# Nikon_PowerBoardV2.net
KiCad netlist of a schematic drawn in EAGLE
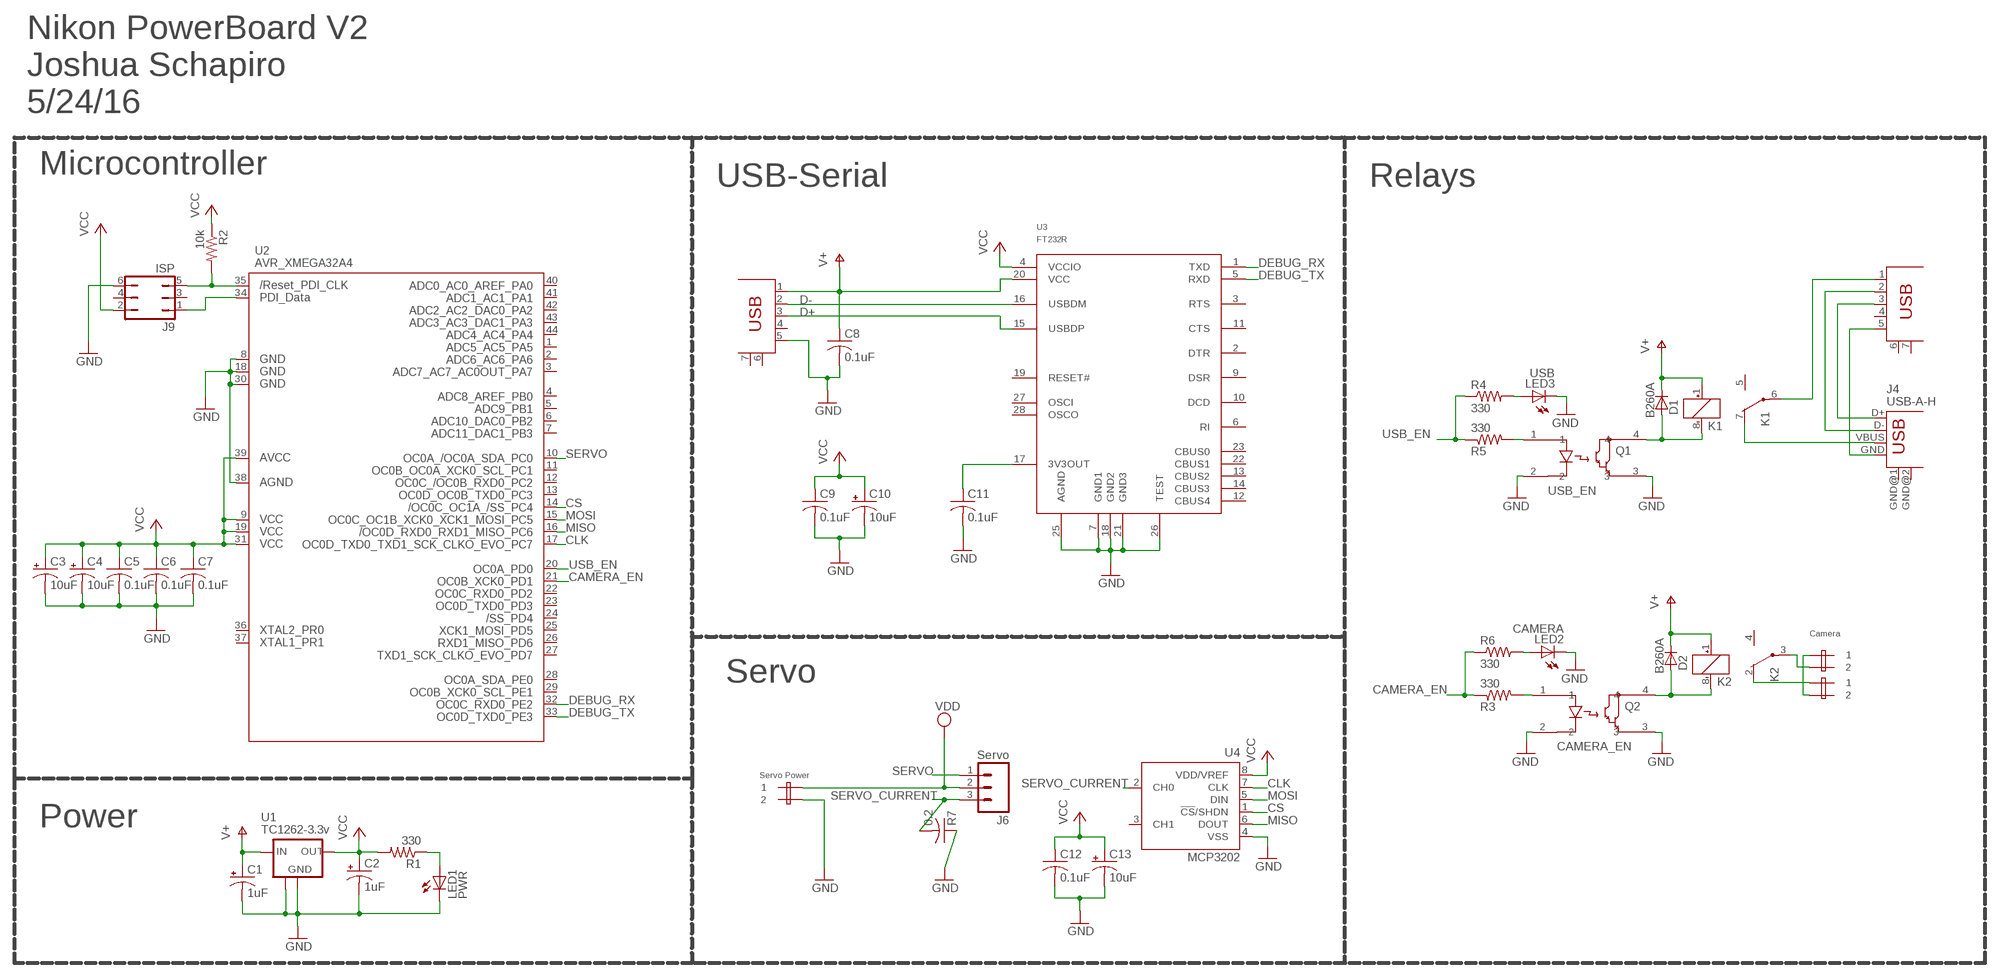
[diagram p0: schematic, sheet 1]

(export (version "E")
  (design (tool "Eeschema 10.0.6"))
  (components
    (comp (ref "C1")
      (value "1uF")
      (footprint "eagle-import:EIA3216")
      (libsource (lib "eagle-import") (part "CAP_POL1206"))
    )
    (comp (ref "C2")
      (value "1uF")
      (footprint "eagle-import:EIA3216")
      (libsource (lib "eagle-import") (part "CAP_POL1206"))
    )
    (comp (ref "C3")
      (value "10uF")
      (footprint "eagle-import:EIA3216")
      (libsource (lib "eagle-import") (part "CAP_POL1206"))
    )
    (comp (ref "C4")
      (value "10uF")
      (footprint "eagle-import:EIA3216")
      (libsource (lib "eagle-import") (part "CAP_POL1206"))
    )
    (comp (ref "C5")
      (value "0.1uF")
      (footprint "eagle-import:C0603")
      (libsource (lib "eagle-import") (part "C-USC0603"))
    )
    (comp (ref "C6")
      (value "0.1uF")
      (footprint "eagle-import:C0603")
      (libsource (lib "eagle-import") (part "resistor_C-USC0603"))
    )
    (comp (ref "C7")
      (value "0.1uF")
      (footprint "eagle-import:C0603")
      (libsource (lib "eagle-import") (part "resistor_C-USC0603"))
    )
    (comp (ref "C8")
      (value "0.1uF")
      (footprint "eagle-import:C0603")
      (libsource (lib "eagle-import") (part "resistor_C-USC0603"))
    )
    (comp (ref "C9")
      (value "0.1uF")
      (footprint "eagle-import:C0603")
      (libsource (lib "eagle-import") (part "resistor_C-USC0603"))
    )
    (comp (ref "C10")
      (value "10uF")
      (footprint "eagle-import:EIA3216")
      (libsource (lib "eagle-import") (part "CAP_POL1206"))
    )
    (comp (ref "C11")
      (value "0.1uF")
      (footprint "eagle-import:C0603")
      (libsource (lib "eagle-import") (part "resistor_C-USC0603"))
    )
    (comp (ref "C12")
      (value "0.1uF")
      (footprint "eagle-import:C0603")
      (libsource (lib "eagle-import") (part "resistor_C-USC0603"))
    )
    (comp (ref "C13")
      (value "10uF")
      (footprint "eagle-import:EIA3216")
      (libsource (lib "eagle-import") (part "CAP_POL1206"))
    )
    (comp (ref "D1")
      (value "B260A")
      (footprint "eagle-import:SMA-DIODE")
      (libsource (lib "eagle-import") (part "DIODESMA"))
    )
    (comp (ref "D2")
      (value "B260A")
      (footprint "eagle-import:SMA-DIODE")
      (libsource (lib "eagle-import") (part "DIODESMA"))
    )
    (comp (ref "J1")
      (value "Camera")
      (footprint "eagle-import:2-PIN_SCREWTERM")
      (libsource (lib "eagle-import") (part "2-PIN_SCREWTERMINAL"))
    )
    (comp (ref "J2")
      (value "Camera")
      (footprint "eagle-import:2-PIN_SCREWTERM")
      (libsource (lib "eagle-import") (part "2-PIN_SCREWTERMINAL"))
    )
    (comp (ref "J4")
      (value "USB-A-H")
      (footprint "eagle-import:USB-A-H")
      (libsource (lib "eagle-import") (part "USB-A-H"))
    )
    (comp (ref "J5")
      (value "SERVO")
      (footprint "eagle-import:2-PIN_SCREWTERM")
      (libsource (lib "eagle-import") (part "2-PIN_SCREWTERMINAL"))
    )
    (comp (ref "J6")
      (value "Servo")
      (footprint "eagle-import:1X03_LONGPADS")
      (libsource (lib "eagle-import") (part "M03LONGPADS"))
    )
    (comp (ref "J7")
      (value "MICRO-USB")
      (footprint "eagle-import:MICRO_USB_SM_W__TO_PINS")
      (libsource (lib "eagle-import") (part "MICRO-USBTO_SUPPORT"))
    )
    (comp (ref "J8")
      (value "MICRO-USB")
      (footprint "eagle-import:MICRO_USB_SM_W__TO_PINS")
      (libsource (lib "eagle-import") (part "MICRO-USBTO_SUPPORT"))
    )
    (comp (ref "J9")
      (value "ISP")
      (footprint "eagle-import:JP3Q")
      (libsource (lib "eagle-import") (part "JP3Q"))
    )
    (comp (ref "K1")
      (value "USB_EN")
      (footprint "eagle-import:G6K-2F")
      (libsource (lib "eagle-import") (part "G6K-2F"))
    )
    (comp (ref "K2")
      (value "CAMERA_EN")
      (footprint "eagle-import:G6K-2F")
      (libsource (lib "eagle-import") (part "G6K-2F"))
    )
    (comp (ref "LED1")
      (value "PWR")
      (footprint "eagle-import:CHIPLED_0603")
      (libsource (lib "eagle-import") (part "LEDCHIPLED_0603"))
    )
    (comp (ref "LED2")
      (value "CAMERA")
      (footprint "eagle-import:CHIPLED_0603")
      (libsource (lib "eagle-import") (part "LEDCHIPLED_0603"))
    )
    (comp (ref "LED3")
      (value "USB")
      (footprint "eagle-import:CHIPLED_0603")
      (libsource (lib "eagle-import") (part "LEDCHIPLED_0603"))
    )
    (comp (ref "Q1")
      (value "USB_EN")
      (footprint "eagle-import:4-PIN_MINI-FLAT")
      (libsource (lib "eagle-import") (part "OPTOISOLATOR_SINGLE"))
    )
    (comp (ref "Q2")
      (value "CAMERA_EN")
      (footprint "eagle-import:4-PIN_MINI-FLAT")
      (libsource (lib "eagle-import") (part "OPTOISOLATOR_SINGLE"))
    )
    (comp (ref "R1")
      (value "330")
      (footprint "eagle-import:R0603")
      (libsource (lib "eagle-import") (part "R-US_R0603"))
    )
    (comp (ref "R2")
      (value "10k")
      (footprint "eagle-import:R0603")
      (libsource (lib "eagle-import") (part "R-US_R0603"))
    )
    (comp (ref "R3")
      (value "330")
      (footprint "eagle-import:R0603")
      (libsource (lib "eagle-import") (part "R-US_R0603"))
    )
    (comp (ref "R4")
      (value "330")
      (footprint "eagle-import:R0603")
      (libsource (lib "eagle-import") (part "R-US_R0603"))
    )
    (comp (ref "R5")
      (value "330")
      (footprint "eagle-import:R0603")
      (libsource (lib "eagle-import") (part "R-US_R0603"))
    )
    (comp (ref "R6")
      (value "330")
      (footprint "eagle-import:R0603")
      (libsource (lib "eagle-import") (part "R-US_R0603"))
    )
    (comp (ref "R7")
      (value "0.2")
      (footprint "eagle-import:C1206")
      (libsource (lib "eagle-import") (part "C-USC1206"))
    )
    (comp (ref "U1")
      (value "TC1262-3.3v")
      (footprint "eagle-import:SOT223")
      (libsource (lib "eagle-import") (part "REGULATOR"))
    )
    (comp (ref "U2")
      (value "AVR_XMEGA32A4")
      (footprint "eagle-import:TQFP44")
      (libsource (lib "eagle-import") (part "AVR_XMEGA_A4_44A"))
    )
    (comp (ref "U3")
      (value "FT232R")
      (footprint "eagle-import:SSOP28")
      (libsource (lib "eagle-import") (part "FT232R"))
    )
    (comp (ref "U4")
      (value "MCP3202")
      (footprint "eagle-import:SO-08")
      (libsource (lib "eagle-import") (part "MCP3202SN"))
    )
  )
  (nets
    (net (code "1") (name "/CAMERA_EN") (class "Default")
      (node (ref "R3") (pin "1") (pinfunction "1_1") (pintype "passive"))
      (node (ref "R6") (pin "1") (pinfunction "1_1") (pintype "passive"))
      (node (ref "U2") (pin "21") (pinfunction "PD1_21") (pintype "bidirectional"))
    )
    (net (code "2") (name "/CLK") (class "Default")
      (node (ref "U2") (pin "17") (pinfunction "PC7_17") (pintype "bidirectional"))
      (node (ref "U4") (pin "7") (pinfunction "CLK_7") (pintype "input"))
    )
    (net (code "3") (name "/CS") (class "Default")
      (node (ref "U2") (pin "14") (pinfunction "PC4_14") (pintype "bidirectional"))
      (node (ref "U4") (pin "1") (pinfunction "~{CS}/SHDN_1") (pintype "input"))
    )
    (net (code "4") (name "/D+") (class "Default")
      (node (ref "J8") (pin "3") (pinfunction "D+_3") (pintype "bidirectional"))
      (node (ref "U3") (pin "15") (pinfunction "USBDP_15") (pintype "bidirectional"))
    )
    (net (code "5") (name "/D-") (class "Default")
      (node (ref "J8") (pin "2") (pinfunction "D-_2") (pintype "bidirectional"))
      (node (ref "U3") (pin "16") (pinfunction "USBDM_16") (pintype "bidirectional"))
    )
    (net (code "6") (name "/DEBUG_RX") (class "Default")
      (node (ref "U2") (pin "32") (pinfunction "PE2_32") (pintype "bidirectional"))
      (node (ref "U3") (pin "1") (pinfunction "TXD_1") (pintype "bidirectional"))
    )
    (net (code "7") (name "/DEBUG_TX") (class "Default")
      (node (ref "U2") (pin "33") (pinfunction "PE3_33") (pintype "bidirectional"))
      (node (ref "U3") (pin "5") (pinfunction "RXD_5") (pintype "bidirectional"))
    )
    (net (code "8") (name "/MISO") (class "Default")
      (node (ref "U2") (pin "16") (pinfunction "PC6_16") (pintype "bidirectional"))
      (node (ref "U4") (pin "6") (pinfunction "DOUT_6") (pintype "input"))
    )
    (net (code "9") (name "/MOSI") (class "Default")
      (node (ref "U2") (pin "15") (pinfunction "PC5_15") (pintype "bidirectional"))
      (node (ref "U4") (pin "5") (pinfunction "DIN_5") (pintype "input"))
    )
    (net (code "10") (name "/SERVO") (class "Default")
      (node (ref "J6") (pin "1") (pinfunction "1_1") (pintype "passive"))
      (node (ref "U2") (pin "10") (pinfunction "PC0_10") (pintype "bidirectional"))
    )
    (net (code "11") (name "/SERVO_CURRENT") (class "Default")
      (node (ref "J6") (pin "3") (pinfunction "3_3") (pintype "passive"))
      (node (ref "R7") (pin "2") (pinfunction "2_2") (pintype "passive"))
      (node (ref "U4") (pin "2") (pinfunction "CH0_2") (pintype "input"))
    )
    (net (code "12") (name "/USB_EN") (class "Default")
      (node (ref "R4") (pin "1") (pinfunction "1_1") (pintype "passive"))
      (node (ref "R5") (pin "1") (pinfunction "1_1") (pintype "passive"))
      (node (ref "U2") (pin "20") (pinfunction "PD0_20") (pintype "bidirectional"))
    )
    (net (code "13") (name "GND") (class "Default")
      (node (ref "C1") (pin "C") (pinfunction "-_C") (pintype "passive"))
      (node (ref "C10") (pin "C") (pinfunction "-_C") (pintype "passive"))
      (node (ref "C11") (pin "2") (pinfunction "2_2") (pintype "passive"))
      (node (ref "C12") (pin "2") (pinfunction "2_2") (pintype "passive"))
      (node (ref "C13") (pin "C") (pinfunction "-_C") (pintype "passive"))
      (node (ref "C2") (pin "C") (pinfunction "-_C") (pintype "passive"))
      (node (ref "C3") (pin "C") (pinfunction "-_C") (pintype "passive"))
      (node (ref "C4") (pin "C") (pinfunction "-_C") (pintype "passive"))
      (node (ref "C5") (pin "2") (pinfunction "2_2") (pintype "passive"))
      (node (ref "C6") (pin "2") (pinfunction "2_2") (pintype "passive"))
      (node (ref "C7") (pin "2") (pinfunction "2_2") (pintype "passive"))
      (node (ref "C8") (pin "2") (pinfunction "2_2") (pintype "passive"))
      (node (ref "C9") (pin "2") (pinfunction "2_2") (pintype "passive"))
      (node (ref "J5") (pin "P$2") (pinfunction "2_P$2") (pintype "bidirectional"))
      (node (ref "J8") (pin "5") (pinfunction "GND_5") (pintype "bidirectional"))
      (node (ref "J9") (pin "6") (pinfunction "6_6") (pintype "passive"))
      (node (ref "LED1") (pin "C") (pinfunction "C_C") (pintype "passive"))
      (node (ref "LED2") (pin "C") (pinfunction "C_C") (pintype "passive"))
      (node (ref "LED3") (pin "C") (pinfunction "C_C") (pintype "passive"))
      (node (ref "Q1") (pin "2") (pinfunction "2_2") (pintype "bidirectional"))
      (node (ref "Q1") (pin "3") (pinfunction "3_3") (pintype "bidirectional"))
      (node (ref "Q2") (pin "2") (pinfunction "2_2") (pintype "bidirectional"))
      (node (ref "Q2") (pin "3") (pinfunction "3_3") (pintype "bidirectional"))
      (node (ref "R7") (pin "1") (pinfunction "1_1") (pintype "passive"))
      (node (ref "U1") (pin "2") (pinfunction "GND_2") (pintype "bidirectional"))
      (node (ref "U1") (pin "4") (pinfunction "GND1_4") (pintype "bidirectional"))
      (node (ref "U2") (pin "18") (pinfunction "GND2_18") (pintype "bidirectional"))
      (node (ref "U2") (pin "30") (pinfunction "GND3_30") (pintype "bidirectional"))
      (node (ref "U2") (pin "38") (pinfunction "AGND_38") (pintype "bidirectional"))
      (node (ref "U2") (pin "8") (pinfunction "GND1_8") (pintype "bidirectional"))
      (node (ref "U3") (pin "18") (pinfunction "GND2_18") (pintype "bidirectional"))
      (node (ref "U3") (pin "21") (pinfunction "GND3_21") (pintype "bidirectional"))
      (node (ref "U3") (pin "25") (pinfunction "AGND_25") (pintype "bidirectional"))
      (node (ref "U3") (pin "26") (pinfunction "TEST_26") (pintype "bidirectional"))
      (node (ref "U3") (pin "7") (pinfunction "GND1_7") (pintype "bidirectional"))
      (node (ref "U4") (pin "4") (pinfunction "VSS_4") (pintype "input"))
    )
    (net (code "14") (name "Net-(J1-1)") (class "Default")
      (node (ref "J1") (pin "P$1") (pinfunction "1_P$1") (pintype "bidirectional"))
      (node (ref "K2") (pin "2") (pinfunction "O_2") (pintype "passive"))
    )
    (net (code "15") (name "Net-(J1-2)") (class "Default")
      (node (ref "J1") (pin "P$2") (pinfunction "2_P$2") (pintype "bidirectional"))
      (node (ref "J2") (pin "P$1") (pinfunction "1_P$1") (pintype "bidirectional"))
    )
    (net (code "16") (name "Net-(J2-2)") (class "Default")
      (node (ref "J2") (pin "P$2") (pinfunction "2_P$2") (pintype "bidirectional"))
      (node (ref "K2") (pin "3") (pinfunction "P_3") (pintype "passive"))
    )
    (net (code "17") (name "Net-(J7-D+)") (class "Default")
      (node (ref "J4") (pin "D+") (pinfunction "D+_D+") (pintype "bidirectional"))
      (node (ref "J7") (pin "3") (pinfunction "D+_3") (pintype "bidirectional"))
    )
    (net (code "18") (name "Net-(J7-D-)") (class "Default")
      (node (ref "J4") (pin "D-") (pinfunction "D-_D-") (pintype "bidirectional"))
      (node (ref "J7") (pin "2") (pinfunction "D-_2") (pintype "bidirectional"))
    )
    (net (code "19") (name "Net-(J7-GND)") (class "Default")
      (node (ref "J4") (pin "GND") (pinfunction "GND_GND") (pintype "bidirectional"))
      (node (ref "J7") (pin "5") (pinfunction "GND_5") (pintype "bidirectional"))
    )
    (net (code "20") (name "Net-(J7-VBUS)") (class "Default")
      (node (ref "J7") (pin "1") (pinfunction "VBUS_1") (pintype "bidirectional"))
      (node (ref "K1") (pin "6") (pinfunction "P_6") (pintype "passive"))
    )
    (net (code "21") (name "Net-(K1A--)") (class "Default")
      (node (ref "D1") (pin "A") (pinfunction "A_A") (pintype "passive"))
      (node (ref "K1") (pin "8") (pinfunction "-_8") (pintype "passive"))
      (node (ref "Q1") (pin "4") (pinfunction "4_4") (pintype "bidirectional"))
    )
    (net (code "22") (name "Net-(K1C-O)") (class "Default")
      (node (ref "J4") (pin "VBUS") (pinfunction "VBUS_VBUS") (pintype "bidirectional"))
      (node (ref "K1") (pin "7") (pinfunction "O_7") (pintype "passive"))
    )
    (net (code "23") (name "Net-(K2A--)") (class "Default")
      (node (ref "D2") (pin "A") (pinfunction "A_A") (pintype "passive"))
      (node (ref "K2") (pin "8") (pinfunction "-_8") (pintype "passive"))
      (node (ref "Q2") (pin "4") (pinfunction "4_4") (pintype "bidirectional"))
    )
    (net (code "24") (name "Net-(LED1-PadA)") (class "Default")
      (node (ref "LED1") (pin "A") (pinfunction "A_A") (pintype "passive"))
      (node (ref "R1") (pin "1") (pinfunction "1_1") (pintype "passive"))
    )
    (net (code "25") (name "Net-(LED2-PadA)") (class "Default")
      (node (ref "LED2") (pin "A") (pinfunction "A_A") (pintype "passive"))
      (node (ref "R6") (pin "2") (pinfunction "2_2") (pintype "passive"))
    )
    (net (code "26") (name "Net-(LED3-PadA)") (class "Default")
      (node (ref "LED3") (pin "A") (pinfunction "A_A") (pintype "passive"))
      (node (ref "R4") (pin "2") (pinfunction "2_2") (pintype "passive"))
    )
    (net (code "27") (name "Net-(Q1-Pad1)") (class "Default")
      (node (ref "Q1") (pin "1") (pinfunction "1_1") (pintype "bidirectional"))
      (node (ref "R5") (pin "2") (pinfunction "2_2") (pintype "passive"))
    )
    (net (code "28") (name "Net-(Q2-Pad1)") (class "Default")
      (node (ref "Q2") (pin "1") (pinfunction "1_1") (pintype "bidirectional"))
      (node (ref "R3") (pin "2") (pinfunction "2_2") (pintype "passive"))
    )
    (net (code "29") (name "Net-(U2-PDI_DATA)") (class "Default")
      (node (ref "J9") (pin "1") (pinfunction "1_1") (pintype "passive"))
      (node (ref "U2") (pin "34") (pinfunction "PDI_DATA_34") (pintype "bidirectional"))
    )
    (net (code "30") (name "Net-(U2-RESET)") (class "Default")
      (node (ref "J9") (pin "5") (pinfunction "5_5") (pintype "passive"))
      (node (ref "R2") (pin "2") (pinfunction "2_2") (pintype "passive"))
      (node (ref "U2") (pin "35") (pinfunction "RESET_35") (pintype "bidirectional"))
    )
    (net (code "31") (name "Net-(U3-3V3OUT)") (class "Default")
      (node (ref "C11") (pin "1") (pinfunction "1_1") (pintype "passive"))
      (node (ref "U3") (pin "17") (pinfunction "3V3OUT_17") (pintype "bidirectional"))
    )
    (net (code "32") (name "V+") (class "Default")
      (node (ref "C1") (pin "A") (pinfunction "+_A") (pintype "passive"))
      (node (ref "C8") (pin "1") (pinfunction "1_1") (pintype "passive"))
      (node (ref "D1") (pin "C") (pinfunction "C_C") (pintype "passive"))
      (node (ref "D2") (pin "C") (pinfunction "C_C") (pintype "passive"))
      (node (ref "J8") (pin "1") (pinfunction "VBUS_1") (pintype "bidirectional"))
      (node (ref "K1") (pin "1") (pinfunction "+_1") (pintype "passive"))
      (node (ref "K2") (pin "1") (pinfunction "+_1") (pintype "passive"))
      (node (ref "U1") (pin "1") (pinfunction "IN_1") (pintype "bidirectional"))
      (node (ref "U3") (pin "20") (pinfunction "VCC_20") (pintype "bidirectional"))
    )
    (net (code "33") (name "VCC") (class "Default")
      (node (ref "C10") (pin "A") (pinfunction "+_A") (pintype "passive"))
      (node (ref "C12") (pin "1") (pinfunction "1_1") (pintype "passive"))
      (node (ref "C13") (pin "A") (pinfunction "+_A") (pintype "passive"))
      (node (ref "C2") (pin "A") (pinfunction "+_A") (pintype "passive"))
      (node (ref "C3") (pin "A") (pinfunction "+_A") (pintype "passive"))
      (node (ref "C4") (pin "A") (pinfunction "+_A") (pintype "passive"))
      (node (ref "C5") (pin "1") (pinfunction "1_1") (pintype "passive"))
      (node (ref "C6") (pin "1") (pinfunction "1_1") (pintype "passive"))
      (node (ref "C7") (pin "1") (pinfunction "1_1") (pintype "passive"))
      (node (ref "C9") (pin "1") (pinfunction "1_1") (pintype "passive"))
      (node (ref "J9") (pin "2") (pinfunction "2_2") (pintype "passive"))
      (node (ref "R1") (pin "2") (pinfunction "2_2") (pintype "passive"))
      (node (ref "R2") (pin "1") (pinfunction "1_1") (pintype "passive"))
      (node (ref "U1") (pin "3") (pinfunction "OUT_3") (pintype "bidirectional"))
      (node (ref "U2") (pin "19") (pinfunction "VCC2_19") (pintype "bidirectional"))
      (node (ref "U2") (pin "31") (pinfunction "VCC3_31") (pintype "bidirectional"))
      (node (ref "U2") (pin "39") (pinfunction "AVCC_39") (pintype "bidirectional"))
      (node (ref "U2") (pin "9") (pinfunction "VCC1_9") (pintype "bidirectional"))
      (node (ref "U3") (pin "4") (pinfunction "VCCIO_4") (pintype "bidirectional"))
      (node (ref "U4") (pin "8") (pinfunction "VDD/VREF_8") (pintype "input"))
    )
    (net (code "34") (name "VDD") (class "Default")
      (node (ref "J5") (pin "P$1") (pinfunction "1_P$1") (pintype "bidirectional"))
      (node (ref "J6") (pin "2") (pinfunction "2_2") (pintype "passive"))
    )
    (net (code "35") (name "unconnected-(J4-GND-PadGND@1)") (class "Default")
      (node (ref "J4") (pin "GND@1") (pinfunction "GND_GND@1") (pintype "bidirectional"))
    )
    (net (code "36") (name "unconnected-(J4-GND-PadGND@2)") (class "Default")
      (node (ref "J4") (pin "GND@2") (pinfunction "GND_GND@2") (pintype "bidirectional"))
    )
    (net (code "37") (name "unconnected-(J7-ID-Pad4)") (class "Default")
      (node (ref "J7") (pin "4") (pinfunction "ID_4") (pintype "bidirectional"))
    )
    (net (code "38") (name "unconnected-(J7-MTN3-Pad6)") (class "Default")
      (node (ref "J7") (pin "6") (pinfunction "MTN3_6") (pintype "bidirectional"))
    )
    (net (code "39") (name "unconnected-(J7-MTN4-Pad7)") (class "Default")
      (node (ref "J7") (pin "7") (pinfunction "MTN4_7") (pintype "bidirectional"))
    )
    (net (code "40") (name "unconnected-(J8-ID-Pad4)") (class "Default")
      (node (ref "J8") (pin "4") (pinfunction "ID_4") (pintype "bidirectional"))
    )
    (net (code "41") (name "unconnected-(J8-MTN3-Pad6)") (class "Default")
      (node (ref "J8") (pin "6") (pinfunction "MTN3_6") (pintype "bidirectional"))
    )
    (net (code "42") (name "unconnected-(J8-MTN4-Pad7)") (class "Default")
      (node (ref "J8") (pin "7") (pinfunction "MTN4_7") (pintype "bidirectional"))
    )
    (net (code "43") (name "unconnected-(J9-Pad3)") (class "Default")
      (node (ref "J9") (pin "3") (pinfunction "3_3") (pintype "passive"))
    )
    (net (code "44") (name "unconnected-(J9-Pad4)") (class "Default")
      (node (ref "J9") (pin "4") (pinfunction "4_4") (pintype "passive"))
    )
    (net (code "45") (name "unconnected-(K1C-S-Pad5)") (class "Default")
      (node (ref "K1") (pin "5") (pinfunction "S_5") (pintype "passive"))
    )
    (net (code "46") (name "unconnected-(K2B-S-Pad4)") (class "Default")
      (node (ref "K2") (pin "4") (pinfunction "S_4") (pintype "passive"))
    )
    (net (code "47") (name "unconnected-(U2-PA0-Pad40)") (class "Default")
      (node (ref "U2") (pin "40") (pinfunction "PA0_40") (pintype "bidirectional"))
    )
    (net (code "48") (name "unconnected-(U2-PA1-Pad41)") (class "Default")
      (node (ref "U2") (pin "41") (pinfunction "PA1_41") (pintype "bidirectional"))
    )
    (net (code "49") (name "unconnected-(U2-PA2-Pad42)") (class "Default")
      (node (ref "U2") (pin "42") (pinfunction "PA2_42") (pintype "bidirectional"))
    )
    (net (code "50") (name "unconnected-(U2-PA3-Pad43)") (class "Default")
      (node (ref "U2") (pin "43") (pinfunction "PA3_43") (pintype "bidirectional"))
    )
    (net (code "51") (name "unconnected-(U2-PA4-Pad44)") (class "Default")
      (node (ref "U2") (pin "44") (pinfunction "PA4_44") (pintype "bidirectional"))
    )
    (net (code "52") (name "unconnected-(U2-PA5-Pad1)") (class "Default")
      (node (ref "U2") (pin "1") (pinfunction "PA5_1") (pintype "bidirectional"))
    )
    (net (code "53") (name "unconnected-(U2-PA6-Pad2)") (class "Default")
      (node (ref "U2") (pin "2") (pinfunction "PA6_2") (pintype "bidirectional"))
    )
    (net (code "54") (name "unconnected-(U2-PA7-Pad3)") (class "Default")
      (node (ref "U2") (pin "3") (pinfunction "PA7_3") (pintype "bidirectional"))
    )
    (net (code "55") (name "unconnected-(U2-PB0-Pad4)") (class "Default")
      (node (ref "U2") (pin "4") (pinfunction "PB0_4") (pintype "bidirectional"))
    )
    (net (code "56") (name "unconnected-(U2-PB1-Pad5)") (class "Default")
      (node (ref "U2") (pin "5") (pinfunction "PB1_5") (pintype "bidirectional"))
    )
    (net (code "57") (name "unconnected-(U2-PB2-Pad6)") (class "Default")
      (node (ref "U2") (pin "6") (pinfunction "PB2_6") (pintype "bidirectional"))
    )
    (net (code "58") (name "unconnected-(U2-PB3-Pad7)") (class "Default")
      (node (ref "U2") (pin "7") (pinfunction "PB3_7") (pintype "bidirectional"))
    )
    (net (code "59") (name "unconnected-(U2-PC1-Pad11)") (class "Default")
      (node (ref "U2") (pin "11") (pinfunction "PC1_11") (pintype "bidirectional"))
    )
    (net (code "60") (name "unconnected-(U2-PC2-Pad12)") (class "Default")
      (node (ref "U2") (pin "12") (pinfunction "PC2_12") (pintype "bidirectional"))
    )
    (net (code "61") (name "unconnected-(U2-PC3-Pad13)") (class "Default")
      (node (ref "U2") (pin "13") (pinfunction "PC3_13") (pintype "bidirectional"))
    )
    (net (code "62") (name "unconnected-(U2-PD2-Pad22)") (class "Default")
      (node (ref "U2") (pin "22") (pinfunction "PD2_22") (pintype "bidirectional"))
    )
    (net (code "63") (name "unconnected-(U2-PD3-Pad23)") (class "Default")
      (node (ref "U2") (pin "23") (pinfunction "PD3_23") (pintype "bidirectional"))
    )
    (net (code "64") (name "unconnected-(U2-PD4-Pad24)") (class "Default")
      (node (ref "U2") (pin "24") (pinfunction "PD4_24") (pintype "bidirectional"))
    )
    (net (code "65") (name "unconnected-(U2-PD5-Pad25)") (class "Default")
      (node (ref "U2") (pin "25") (pinfunction "PD5_25") (pintype "bidirectional"))
    )
    (net (code "66") (name "unconnected-(U2-PD6-Pad26)") (class "Default")
      (node (ref "U2") (pin "26") (pinfunction "PD6_26") (pintype "bidirectional"))
    )
    (net (code "67") (name "unconnected-(U2-PD7-Pad27)") (class "Default")
      (node (ref "U2") (pin "27") (pinfunction "PD7_27") (pintype "bidirectional"))
    )
    (net (code "68") (name "unconnected-(U2-PE0-Pad28)") (class "Default")
      (node (ref "U2") (pin "28") (pinfunction "PE0_28") (pintype "bidirectional"))
    )
    (net (code "69") (name "unconnected-(U2-PE1-Pad29)") (class "Default")
      (node (ref "U2") (pin "29") (pinfunction "PE1_29") (pintype "bidirectional"))
    )
    (net (code "70") (name "unconnected-(U2-PR0-Pad36)") (class "Default")
      (node (ref "U2") (pin "36") (pinfunction "PR0_36") (pintype "bidirectional"))
    )
    (net (code "71") (name "unconnected-(U2-PR1-Pad37)") (class "Default")
      (node (ref "U2") (pin "37") (pinfunction "PR1_37") (pintype "bidirectional"))
    )
    (net (code "72") (name "unconnected-(U3-CBUS0-Pad23)") (class "Default")
      (node (ref "U3") (pin "23") (pinfunction "CBUS0_23") (pintype "bidirectional"))
    )
    (net (code "73") (name "unconnected-(U3-CBUS1-Pad22)") (class "Default")
      (node (ref "U3") (pin "22") (pinfunction "CBUS1_22") (pintype "bidirectional"))
    )
    (net (code "74") (name "unconnected-(U3-CBUS2-Pad13)") (class "Default")
      (node (ref "U3") (pin "13") (pinfunction "CBUS2_13") (pintype "bidirectional"))
    )
    (net (code "75") (name "unconnected-(U3-CBUS3-Pad14)") (class "Default")
      (node (ref "U3") (pin "14") (pinfunction "CBUS3_14") (pintype "bidirectional"))
    )
    (net (code "76") (name "unconnected-(U3-CBUS4-Pad12)") (class "Default")
      (node (ref "U3") (pin "12") (pinfunction "CBUS4_12") (pintype "bidirectional"))
    )
    (net (code "77") (name "unconnected-(U3-CTS-Pad11)") (class "Default")
      (node (ref "U3") (pin "11") (pinfunction "CTS_11") (pintype "bidirectional"))
    )
    (net (code "78") (name "unconnected-(U3-DCD-Pad10)") (class "Default")
      (node (ref "U3") (pin "10") (pinfunction "DCD_10") (pintype "bidirectional"))
    )
    (net (code "79") (name "unconnected-(U3-DSR-Pad9)") (class "Default")
      (node (ref "U3") (pin "9") (pinfunction "DSR_9") (pintype "bidirectional"))
    )
    (net (code "80") (name "unconnected-(U3-DTR-Pad2)") (class "Default")
      (node (ref "U3") (pin "2") (pinfunction "DTR_2") (pintype "bidirectional"))
    )
    (net (code "81") (name "unconnected-(U3-OSCI-Pad27)") (class "Default")
      (node (ref "U3") (pin "27") (pinfunction "OSCI_27") (pintype "bidirectional"))
    )
    (net (code "82") (name "unconnected-(U3-OSCO-Pad28)") (class "Default")
      (node (ref "U3") (pin "28") (pinfunction "OSCO_28") (pintype "bidirectional"))
    )
    (net (code "83") (name "unconnected-(U3-RESET#-Pad19)") (class "Default")
      (node (ref "U3") (pin "19") (pinfunction "RESET#_19") (pintype "bidirectional"))
    )
    (net (code "84") (name "unconnected-(U3-RI-Pad6)") (class "Default")
      (node (ref "U3") (pin "6") (pinfunction "RI_6") (pintype "bidirectional"))
    )
    (net (code "85") (name "unconnected-(U3-RTS-Pad3)") (class "Default")
      (node (ref "U3") (pin "3") (pinfunction "RTS_3") (pintype "bidirectional"))
    )
    (net (code "86") (name "unconnected-(U4-CH1-Pad3)") (class "Default")
      (node (ref "U4") (pin "3") (pinfunction "CH1_3") (pintype "input"))
    )
  )
)
